# Relay_and_connector.net
KiCad netlist of a schematic drawn in Altium Designer
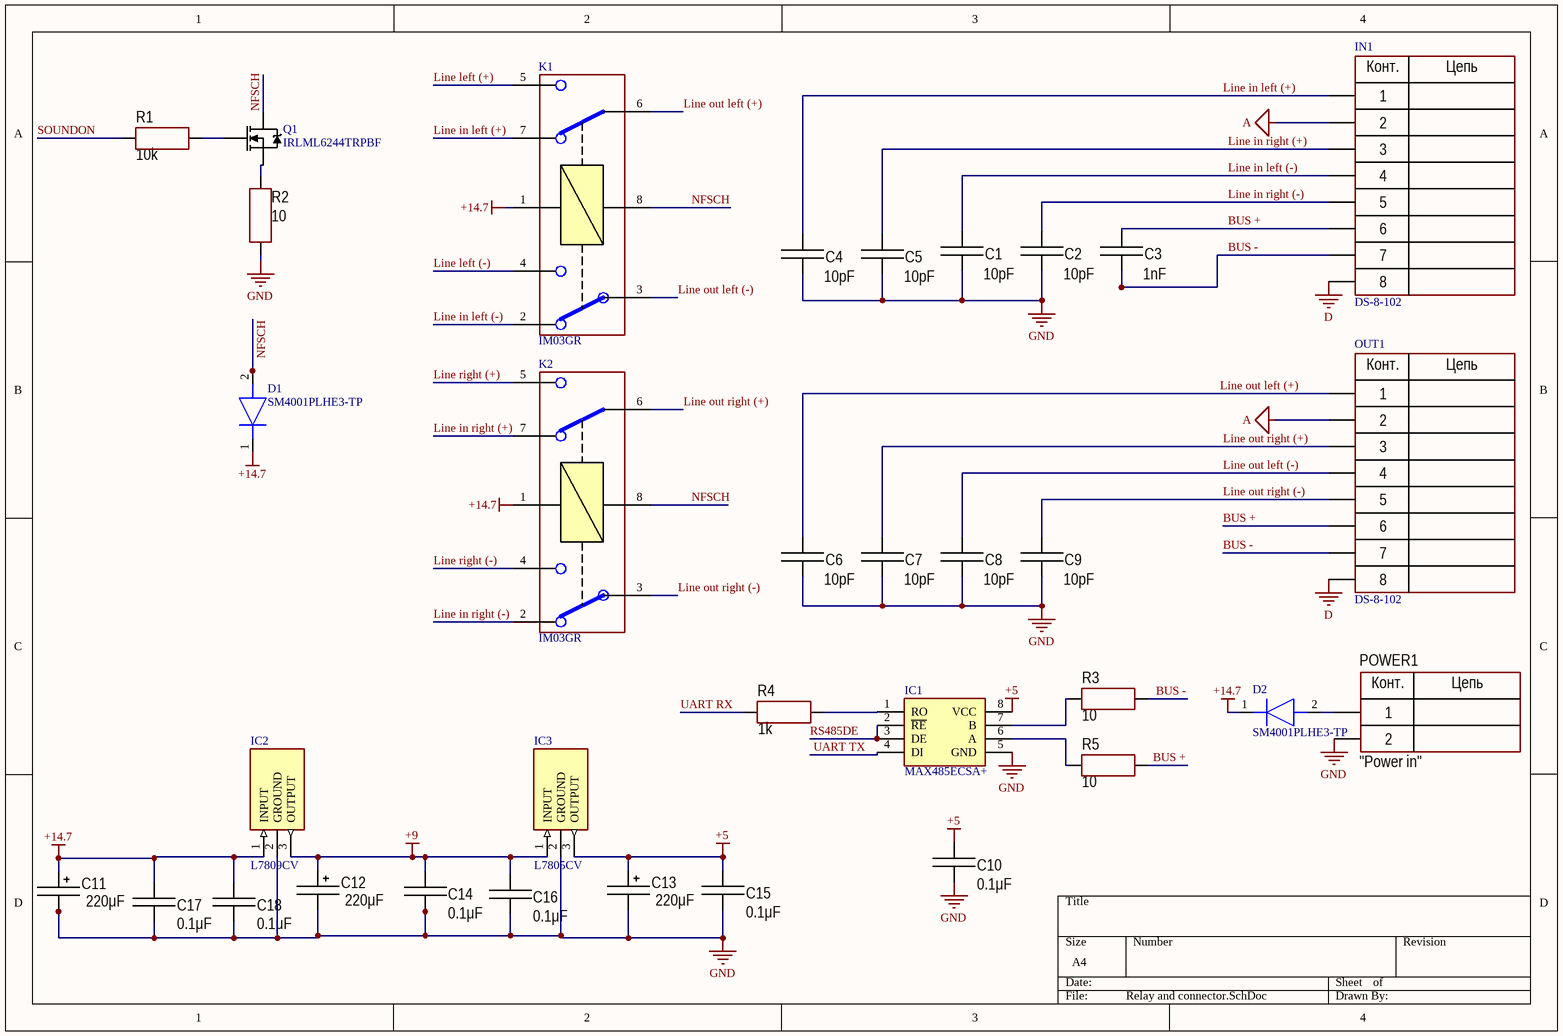
[diagram p0: Relay and connector.SchDoc]

(export (version "E")
  (design (tool "Eeschema 10.0.6"))
  (components
    (comp (ref "C1")
      (value "10pF")
      (footprint "CAP: 0805")
      (fields
        (field (name "MANUFACTURER") "Yageo")
        (field (name "PARTNUMBER") "CC0805KRX7R7BB104")
        (field (name "VALUEMANUFACTURERPARTNUMBER") "Ceramic capacitor, 10pF, X7R, ±10%, 16V, 0805, -55...+125°C")
      )
      (libsource (lib "capacitor") (part "Ceramic_0805"))
    )
    (comp (ref "C2")
      (value "10pF")
      (footprint "CAP: 0805")
      (fields
        (field (name "MANUFACTURER") "Yageo")
        (field (name "PARTNUMBER") "CC0805KRX7R7BB104")
        (field (name "VALUEMANUFACTURERPARTNUMBER") "Ceramic capacitor, 10pF, X7R, ±10%, 16V, 0805, -55...+125°C")
      )
      (libsource (lib "capacitor") (part "Ceramic_0805"))
    )
    (comp (ref "C3")
      (value "1nF")
      (footprint "CAP: 0805")
      (fields
        (field (name "MANUFACTURER") "Yageo")
        (field (name "PARTNUMBER") "CC0805KRX7R7BB104")
        (field (name "VALUEMANUFACTURERPARTNUMBER") "Ceramic capacitor, 1nF, X7R, ±10%, 16V, 0805, -55...+125°C")
      )
      (libsource (lib "capacitor") (part "Ceramic_0805"))
    )
    (comp (ref "C4")
      (value "10pF")
      (footprint "CAP: 0805")
      (fields
        (field (name "MANUFACTURER") "Yageo")
        (field (name "PARTNUMBER") "CC0805KRX7R7BB104")
        (field (name "VALUEMANUFACTURERPARTNUMBER") "Ceramic capacitor, 10pF, X7R, ±10%, 16V, 0805, -55...+125°C")
      )
      (libsource (lib "capacitor") (part "Ceramic_0805"))
    )
    (comp (ref "C5")
      (value "10pF")
      (footprint "CAP: 0805")
      (fields
        (field (name "MANUFACTURER") "Yageo")
        (field (name "PARTNUMBER") "CC0805KRX7R7BB104")
        (field (name "VALUEMANUFACTURERPARTNUMBER") "Ceramic capacitor, 10pF, X7R, ±10%, 16V, 0805, -55...+125°C")
      )
      (libsource (lib "capacitor") (part "Ceramic_0805"))
    )
    (comp (ref "C6")
      (value "10pF")
      (footprint "CAP: 0805")
      (fields
        (field (name "MANUFACTURER") "Yageo")
        (field (name "PARTNUMBER") "CC0805KRX7R7BB104")
        (field (name "VALUEMANUFACTURERPARTNUMBER") "Ceramic capacitor, 10pF, X7R, ±10%, 16V, 0805, -55...+125°C")
      )
      (libsource (lib "capacitor") (part "Ceramic_0805"))
    )
    (comp (ref "C7")
      (value "10pF")
      (footprint "CAP: 0805")
      (fields
        (field (name "MANUFACTURER") "Yageo")
        (field (name "PARTNUMBER") "CC0805KRX7R7BB104")
        (field (name "VALUEMANUFACTURERPARTNUMBER") "Ceramic capacitor, 10pF, X7R, ±10%, 16V, 0805, -55...+125°C")
      )
      (libsource (lib "capacitor") (part "Ceramic_0805"))
    )
    (comp (ref "C8")
      (value "10pF")
      (footprint "CAP: 0805")
      (fields
        (field (name "MANUFACTURER") "Yageo")
        (field (name "PARTNUMBER") "CC0805KRX7R7BB104")
        (field (name "VALUEMANUFACTURERPARTNUMBER") "Ceramic capacitor, 10pF, X7R, ±10%, 16V, 0805, -55...+125°C")
      )
      (libsource (lib "capacitor") (part "Ceramic_0805"))
    )
    (comp (ref "C9")
      (value "10pF")
      (footprint "CAP: 0805")
      (fields
        (field (name "MANUFACTURER") "Yageo")
        (field (name "PARTNUMBER") "CC0805KRX7R7BB104")
        (field (name "VALUEMANUFACTURERPARTNUMBER") "Ceramic capacitor, 10pF, X7R, ±10%, 16V, 0805, -55...+125°C")
      )
      (libsource (lib "capacitor") (part "Ceramic_0805"))
    )
    (comp (ref "C10")
      (value "0.1μF")
      (footprint "CAP: 0805")
      (fields
        (field (name "MANUFACTURER") "Yageo")
        (field (name "PARTNUMBER") "CC0805KRX7R7BB104")
        (field (name "VALUEMANUFACTURERPARTNUMBER") "Ceramic capacitor, 0.1μF, X7R, ±10%, , 0805, -55...+125°C")
      )
      (libsource (lib "capacitor") (part "Ceramic_0805"))
    )
    (comp (ref "C11")
      (value "220μF")
      (footprint "CAP: D10C5H20")
      (fields
        (field (name "MANUFACTURER") "Wurth")
        (field (name "PARTNUMBER") "860080475013")
        (field (name "VALUEMANUFACTURERPARTNUMBER") "Aluminium capacitor, 220μF, 25V, ±20%, 54mOhm, 14x10x5 mm, -55...+105°C")
      )
      (libsource (lib "capacitor") (part "Aluminium"))
    )
    (comp (ref "C12")
      (value "220μF")
      (footprint "CAP: D10C5H20")
      (fields
        (field (name "MANUFACTURER") "Wurth")
        (field (name "PARTNUMBER") "860080475013")
        (field (name "VALUEMANUFACTURERPARTNUMBER") "Aluminium capacitor, 220μF, 25V, ±20%, 54mOhm, 14x10x5 mm, -55...+105°C")
      )
      (libsource (lib "capacitor") (part "Aluminium"))
    )
    (comp (ref "C13")
      (value "220μF")
      (footprint "CAP: D10C5H20")
      (fields
        (field (name "MANUFACTURER") "Wurth")
        (field (name "PARTNUMBER") "860080475013")
        (field (name "VALUEMANUFACTURERPARTNUMBER") "Aluminium capacitor, 220μF, 25V, ±20%, 54mOhm, 14x10x5 mm, -55...+105°C")
      )
      (libsource (lib "capacitor") (part "Aluminium"))
    )
    (comp (ref "C14")
      (value "0.1μF")
      (footprint "CAP: 0805")
      (fields
        (field (name "MANUFACTURER") "Yageo")
        (field (name "PARTNUMBER") "CC0805KRX7R7BB104")
        (field (name "VALUEMANUFACTURERPARTNUMBER") "Ceramic capacitor, 0.1μF, X7R, ±10%, , 0805, -55...+125°C")
      )
      (libsource (lib "capacitor") (part "Ceramic_0805"))
    )
    (comp (ref "C15")
      (value "0.1μF")
      (footprint "CAP: 0805")
      (fields
        (field (name "MANUFACTURER") "Yageo")
        (field (name "PARTNUMBER") "CC0805KRX7R7BB104")
        (field (name "VALUEMANUFACTURERPARTNUMBER") "Ceramic capacitor, 0.1μF, X7R, ±10%, , 0805, -55...+125°C")
      )
      (libsource (lib "capacitor") (part "Ceramic_0805"))
    )
    (comp (ref "C16")
      (value "0.1μF")
      (footprint "CAP: 0805")
      (fields
        (field (name "MANUFACTURER") "Yageo")
        (field (name "PARTNUMBER") "CC0805KRX7R7BB104")
        (field (name "VALUEMANUFACTURERPARTNUMBER") "Ceramic capacitor, 0.1μF, X7R, ±10%, , 0805, -55...+125°C")
      )
      (libsource (lib "capacitor") (part "Ceramic_0805"))
    )
    (comp (ref "C17")
      (value "0.1μF")
      (footprint "CAP: 0805")
      (fields
        (field (name "MANUFACTURER") "Yageo")
        (field (name "PARTNUMBER") "CC0805KRX7R7BB104")
        (field (name "VALUEMANUFACTURERPARTNUMBER") "Ceramic capacitor, 0.1μF, X7R, ±10%, , 0805, -55...+125°C")
      )
      (libsource (lib "capacitor") (part "Ceramic_0805"))
    )
    (comp (ref "C18")
      (value "0.1μF")
      (footprint "CAP: 0805")
      (fields
        (field (name "MANUFACTURER") "Yageo")
        (field (name "PARTNUMBER") "CC0805KRX7R7BB104")
        (field (name "VALUEMANUFACTURERPARTNUMBER") "Ceramic capacitor, 0.1μF, X7R, ±10%, , 0805, -55...+125°C")
      )
      (libsource (lib "capacitor") (part "Ceramic_0805"))
    )
    (comp (ref "D1")
      (value "SM4001PLHE3-TP")
      (footprint "SamacSys:SODFL3616X135N")
      (description "Diode")
      (fields (field (name "MOUSER PART NUMBER") "833-SM4001PLHE3-TP"))
      (libsource (lib "*") (part "SM4001PLHE3-TP"))
    )
    (comp (ref "D2")
      (value "SM4001PLHE3-TP")
      (footprint "SamacSys:SODFL3616X135N")
      (description "Diode")
      (fields (field (name "MOUSER PART NUMBER") "833-SM4001PLHE3-TP"))
      (libsource (lib "*") (part "SM4001PLHE3-TP"))
    )
    (comp (ref "IC1")
      (value "MAX485ECSA+")
      (footprint "SamacSys:SOIC127P600X175-8N")
      (description "Integrated Circuit")
      (fields (field (name "MOUSER PART NUMBER") "700-MAX485ECSA"))
      (libsource (lib "*") (part "MAX485ECSA+"))
    )
    (comp (ref "IC2")
      (value "L7809CV")
      (footprint "SamacSys:TO255P460X1020X2008-3P")
      (description "Integrated Circuit")
      (fields (field (name "MOUSER PART NUMBER") "511-L7809CV"))
      (libsource (lib "SamacSys") (part "L7809CV"))
    )
    (comp (ref "IC3")
      (value "L7805CV")
      (footprint "SamacSys:TO255P460X1020X2008-3P")
      (description "Integrated Circuit")
      (fields (field (name "MOUSER PART NUMBER") "511-L7805CV"))
      (libsource (lib "SamacSys") (part "L7805CV"))
    )
    (comp (ref "IN1") (value "DS-8-102") (footprint "DS-8-102") (libsource (lib "DIN 8") (part "DS-8-102")))
    (comp (ref "K1")
      (value "IM03GR")
      (footprint "SamacSys:IM06GR")
      (description "Relay or Contactor")
      (fields (field (name "MOUSER PART NUMBER") "655-IM03GR"))
      (libsource (lib "SamacSys") (part "IM03GR"))
    )
    (comp (ref "K2")
      (value "IM03GR")
      (footprint "SamacSys:IM06GR")
      (description "Relay or Contactor")
      (fields (field (name "MOUSER PART NUMBER") "655-IM03GR"))
      (libsource (lib "SamacSys") (part "IM03GR"))
    )
    (comp (ref "OUT1") (value "DS-8-102") (footprint "DS-8-102") (libsource (lib "DIN 8") (part "DS-8-102")))
    (comp (ref "POWER1")
      (value "~")
      (footprint "CON: CWF-2")
      (fields
        (field (name "MANUFACTURER") "Connfly")
        (field (name "VALUEMANUFACTURERPARTNUMBER") "Connector, 2pin, 2.54mm, 250VAC, 3A")
        (field (name "PARTNUMBER") "CWF-2R")
        (field (name "COMMENTTEXT") "\"Power in\"")
      )
      (libsource (lib "connector") (part "CWF-2"))
    )
    (comp (ref "Q1")
      (value "IRLML6244TRPBF")
      (footprint "SamacSys:SOT95P237X112-3N")
      (description "Transistor")
      (fields (field (name "MOUSER PART NUMBER") "942-IRLML6244TRPBF"))
      (libsource (lib "SamacSys") (part "IRLML6244TRPBF"))
    )
    (comp (ref "R1")
      (value "10k")
      (footprint "RES: 0805")
      (fields
        (field (name "MANUFACTURER") "Yageo")
        (field (name "PARTNUMBER") "RC0805JR-07100RL")
        (field (name "VALUEMANUFACTURERPARTNUMBER") "Resistor film, 10k, ±5%, 0805, 0.125W, -55...+125°C")
      )
      (libsource (lib "") (part "Resistor_0805_1"))
    )
    (comp (ref "R2")
      (value "10")
      (footprint "RES: 0805")
      (fields
        (field (name "MANUFACTURER") "Yageo")
        (field (name "PARTNUMBER") "RC0805JR-07100RL")
        (field (name "VALUEMANUFACTURERPARTNUMBER") "Resistor film, 10, ±5%, 0805, 0.125W, -55...+125°C")
      )
      (libsource (lib "resistor") (part "Resistor_0805"))
    )
    (comp (ref "R3")
      (value "10")
      (footprint "RES: 0805")
      (fields
        (field (name "MANUFACTURER") "Yageo")
        (field (name "PARTNUMBER") "RC0805JR-07100RL")
        (field (name "VALUEMANUFACTURERPARTNUMBER") "Resistor film, 10, ±5%, 0805, 0.125W, -55...+125°C")
      )
      (libsource (lib "") (part "Resistor_0805_1"))
    )
    (comp (ref "R4")
      (value "1k")
      (footprint "RES: 0805")
      (fields
        (field (name "MANUFACTURER") "Yageo")
        (field (name "PARTNUMBER") "RC0805JR-07100RL")
        (field (name "VALUEMANUFACTURERPARTNUMBER") "Resistor film, 1k, ±5%, 0805, 0.125W, -55...+125°C")
      )
      (libsource (lib "") (part "Resistor_0805_1"))
    )
    (comp (ref "R5")
      (value "10")
      (footprint "RES: 0805")
      (fields
        (field (name "MANUFACTURER") "Yageo")
        (field (name "PARTNUMBER") "RC0805JR-07100RL")
        (field (name "VALUEMANUFACTURERPARTNUMBER") "Resistor film, 10, ±5%, 0805, 0.125W, -55...+125°C")
      )
      (libsource (lib "") (part "Resistor_0805_1"))
    )
  )
  (nets
    (net (code "1") (name "+5") (class "Default")
      (node (ref "C10") (pin "1") (pinfunction "1_1") (pintype "passive"))
      (node (ref "C13") (pin "1") (pinfunction "1_1") (pintype "passive"))
      (node (ref "C15") (pin "1") (pinfunction "1_1") (pintype "passive"))
      (node (ref "IC1") (pin "8") (pinfunction "VCC_8") (pintype "passive"))
      (node (ref "IC3") (pin "3") (pinfunction "OUTPUT_3") (pintype "output"))
    )
    (net (code "2") (name "+9") (class "Default")
      (node (ref "C12") (pin "1") (pinfunction "1_1") (pintype "passive"))
      (node (ref "C14") (pin "1") (pinfunction "1_1") (pintype "passive"))
      (node (ref "C16") (pin "1") (pinfunction "1_1") (pintype "passive"))
      (node (ref "IC2") (pin "3") (pinfunction "OUTPUT_3") (pintype "output"))
      (node (ref "IC3") (pin "1") (pinfunction "INPUT_1") (pintype "input"))
    )
    (net (code "3") (name "+14.7") (class "Default")
      (node (ref "C11") (pin "1") (pinfunction "1_1") (pintype "passive"))
      (node (ref "C17") (pin "1") (pinfunction "1_1") (pintype "passive"))
      (node (ref "C18") (pin "1") (pinfunction "1_1") (pintype "passive"))
      (node (ref "D1") (pin "1") (pinfunction "K_1") (pintype "passive"))
      (node (ref "D2") (pin "1") (pinfunction "K_1") (pintype "passive"))
      (node (ref "IC2") (pin "1") (pinfunction "INPUT_1") (pintype "input"))
      (node (ref "K1") (pin "1") (pinfunction "1_1") (pintype "passive"))
      (node (ref "K2") (pin "1") (pinfunction "1_1") (pintype "passive"))
    )
    (net (code "4") (name "/BUS +") (class "Default")
      (node (ref "C3") (pin "2") (pinfunction "2_2") (pintype "passive"))
      (node (ref "IN1") (pin "6") (pinfunction "6_6") (pintype "power_in"))
      (node (ref "OUT1") (pin "6") (pinfunction "6_6") (pintype "power_in"))
      (node (ref "R5") (pin "2") (pinfunction "2_2") (pintype "passive"))
    )
    (net (code "5") (name "/BUS -") (class "Default")
      (node (ref "C3") (pin "1") (pinfunction "1_1") (pintype "passive"))
      (node (ref "IN1") (pin "7") (pinfunction "7_7") (pintype "power_in"))
      (node (ref "OUT1") (pin "7") (pinfunction "7_7") (pintype "power_in"))
      (node (ref "R3") (pin "2") (pinfunction "2_2") (pintype "passive"))
    )
    (net (code "6") (name "/Line in left (+)") (class "Default")
      (node (ref "C4") (pin "2") (pinfunction "2_2") (pintype "passive"))
      (node (ref "IN1") (pin "1") (pinfunction "1_1") (pintype "passive"))
      (node (ref "K1") (pin "7") (pinfunction "7_7") (pintype "passive"))
    )
    (net (code "7") (name "/Line in left (-)") (class "Default")
      (node (ref "C1") (pin "2") (pinfunction "2_2") (pintype "passive"))
      (node (ref "IN1") (pin "4") (pinfunction "4_4") (pintype "power_in"))
      (node (ref "K1") (pin "2") (pinfunction "2_2") (pintype "passive"))
    )
    (net (code "8") (name "/Line in right (+)") (class "Default")
      (node (ref "C5") (pin "2") (pinfunction "2_2") (pintype "passive"))
      (node (ref "IN1") (pin "3") (pinfunction "3_3") (pintype "power_in"))
      (node (ref "K2") (pin "7") (pinfunction "7_7") (pintype "passive"))
    )
    (net (code "9") (name "/Line in right (-)") (class "Default")
      (node (ref "C2") (pin "2") (pinfunction "2_2") (pintype "passive"))
      (node (ref "IN1") (pin "5") (pinfunction "5_5") (pintype "power_in"))
      (node (ref "K2") (pin "2") (pinfunction "2_2") (pintype "passive"))
    )
    (net (code "10") (name "/Line left (+)") (class "Default")
      (node (ref "K1") (pin "5") (pinfunction "5_5") (pintype "passive"))
    )
    (net (code "11") (name "/Line left (-)") (class "Default")
      (node (ref "K1") (pin "4") (pinfunction "4_4") (pintype "passive"))
    )
    (net (code "12") (name "/Line out left (+)") (class "Default")
      (node (ref "C6") (pin "2") (pinfunction "2_2") (pintype "passive"))
      (node (ref "K1") (pin "6") (pinfunction "6_6") (pintype "passive"))
      (node (ref "OUT1") (pin "1") (pinfunction "1_1") (pintype "passive"))
    )
    (net (code "13") (name "/Line out left (-)") (class "Default")
      (node (ref "C8") (pin "2") (pinfunction "2_2") (pintype "passive"))
      (node (ref "K1") (pin "3") (pinfunction "3_3") (pintype "passive"))
      (node (ref "OUT1") (pin "4") (pinfunction "4_4") (pintype "power_in"))
    )
    (net (code "14") (name "/Line out right (+)") (class "Default")
      (node (ref "C7") (pin "2") (pinfunction "2_2") (pintype "passive"))
      (node (ref "K2") (pin "6") (pinfunction "6_6") (pintype "passive"))
      (node (ref "OUT1") (pin "3") (pinfunction "3_3") (pintype "power_in"))
    )
    (net (code "15") (name "/Line out right (-)") (class "Default")
      (node (ref "C9") (pin "2") (pinfunction "2_2") (pintype "passive"))
      (node (ref "K2") (pin "3") (pinfunction "3_3") (pintype "passive"))
      (node (ref "OUT1") (pin "5") (pinfunction "5_5") (pintype "power_in"))
    )
    (net (code "16") (name "/Line right (+)") (class "Default")
      (node (ref "K2") (pin "5") (pinfunction "5_5") (pintype "passive"))
    )
    (net (code "17") (name "/Line right (-)") (class "Default")
      (node (ref "K2") (pin "4") (pinfunction "4_4") (pintype "passive"))
    )
    (net (code "18") (name "/NFSCH") (class "Default")
      (node (ref "D1") (pin "2") (pinfunction "A_2") (pintype "passive"))
      (node (ref "K1") (pin "8") (pinfunction "8_8") (pintype "passive"))
      (node (ref "K2") (pin "8") (pinfunction "8_8") (pintype "passive"))
      (node (ref "Q1") (pin "3") (pinfunction "D_3") (pintype "passive"))
    )
    (net (code "19") (name "/RS485DE") (class "Default")
      (node (ref "IC1") (pin "2") (pinfunction "~{RE}_2") (pintype "passive"))
      (node (ref "IC1") (pin "3") (pinfunction "DE_3") (pintype "passive"))
    )
    (net (code "20") (name "/SOUNDON") (class "Default")
      (node (ref "R1") (pin "1") (pinfunction "1_1") (pintype "passive"))
    )
    (net (code "21") (name "/UART RX") (class "Default")
      (node (ref "R4") (pin "1") (pinfunction "1_1") (pintype "passive"))
    )
    (net (code "22") (name "/UART TX") (class "Default")
      (node (ref "IC1") (pin "4") (pinfunction "DI_4") (pintype "passive"))
    )
    (net (code "23") (name "A") (class "Default")
      (node (ref "IN1") (pin "2") (pinfunction "2_2") (pintype "passive"))
      (node (ref "OUT1") (pin "2") (pinfunction "2_2") (pintype "passive"))
    )
    (net (code "24") (name "D") (class "Default")
      (node (ref "IN1") (pin "8") (pinfunction "8_8") (pintype "power_in"))
      (node (ref "OUT1") (pin "8") (pinfunction "8_8") (pintype "power_in"))
    )
    (net (code "25") (name "GND") (class "Default")
      (node (ref "C1") (pin "1") (pinfunction "1_1") (pintype "passive"))
      (node (ref "C10") (pin "2") (pinfunction "2_2") (pintype "passive"))
      (node (ref "C11") (pin "2") (pinfunction "2_2") (pintype "passive"))
      (node (ref "C12") (pin "2") (pinfunction "2_2") (pintype "passive"))
      (node (ref "C13") (pin "2") (pinfunction "2_2") (pintype "passive"))
      (node (ref "C14") (pin "2") (pinfunction "2_2") (pintype "passive"))
      (node (ref "C15") (pin "2") (pinfunction "2_2") (pintype "passive"))
      (node (ref "C16") (pin "2") (pinfunction "2_2") (pintype "passive"))
      (node (ref "C17") (pin "2") (pinfunction "2_2") (pintype "passive"))
      (node (ref "C18") (pin "2") (pinfunction "2_2") (pintype "passive"))
      (node (ref "C2") (pin "1") (pinfunction "1_1") (pintype "passive"))
      (node (ref "C4") (pin "1") (pinfunction "1_1") (pintype "passive"))
      (node (ref "C5") (pin "1") (pinfunction "1_1") (pintype "passive"))
      (node (ref "C6") (pin "1") (pinfunction "1_1") (pintype "passive"))
      (node (ref "C7") (pin "1") (pinfunction "1_1") (pintype "passive"))
      (node (ref "C8") (pin "1") (pinfunction "1_1") (pintype "passive"))
      (node (ref "C9") (pin "1") (pinfunction "1_1") (pintype "passive"))
      (node (ref "IC1") (pin "5") (pinfunction "GND_5") (pintype "passive"))
      (node (ref "IC2") (pin "2") (pinfunction "GROUND_2") (pintype "passive"))
      (node (ref "IC3") (pin "2") (pinfunction "GROUND_2") (pintype "passive"))
      (node (ref "POWER1") (pin "2") (pinfunction "2_2") (pintype "passive"))
      (node (ref "R2") (pin "1") (pinfunction "1_1") (pintype "passive"))
    )
    (net (code "26") (name "Net-(D2-A)") (class "Default")
      (node (ref "D2") (pin "2") (pinfunction "A_2") (pintype "passive"))
      (node (ref "POWER1") (pin "1") (pinfunction "1_1") (pintype "passive"))
    )
    (net (code "27") (name "Net-(IC1-A)") (class "Default")
      (node (ref "IC1") (pin "6") (pinfunction "A_6") (pintype "passive"))
      (node (ref "R5") (pin "1") (pinfunction "1_1") (pintype "passive"))
    )
    (net (code "28") (name "Net-(IC1-B)") (class "Default")
      (node (ref "IC1") (pin "7") (pinfunction "B_7") (pintype "passive"))
      (node (ref "R3") (pin "1") (pinfunction "1_1") (pintype "passive"))
    )
    (net (code "29") (name "Net-(IC1-RO)") (class "Default")
      (node (ref "IC1") (pin "1") (pinfunction "RO_1") (pintype "passive"))
      (node (ref "R4") (pin "2") (pinfunction "2_2") (pintype "passive"))
    )
    (net (code "30") (name "Net-(Q1-G)") (class "Default")
      (node (ref "Q1") (pin "1") (pinfunction "G_1") (pintype "passive"))
      (node (ref "R1") (pin "2") (pinfunction "2_2") (pintype "passive"))
    )
    (net (code "31") (name "Net-(Q1-S)") (class "Default")
      (node (ref "Q1") (pin "2") (pinfunction "S_2") (pintype "passive"))
      (node (ref "R2") (pin "2") (pinfunction "2_2") (pintype "passive"))
    )
  )
)
